# smart-home_matherboard.net
KiCad netlist of a schematic drawn in EAGLE
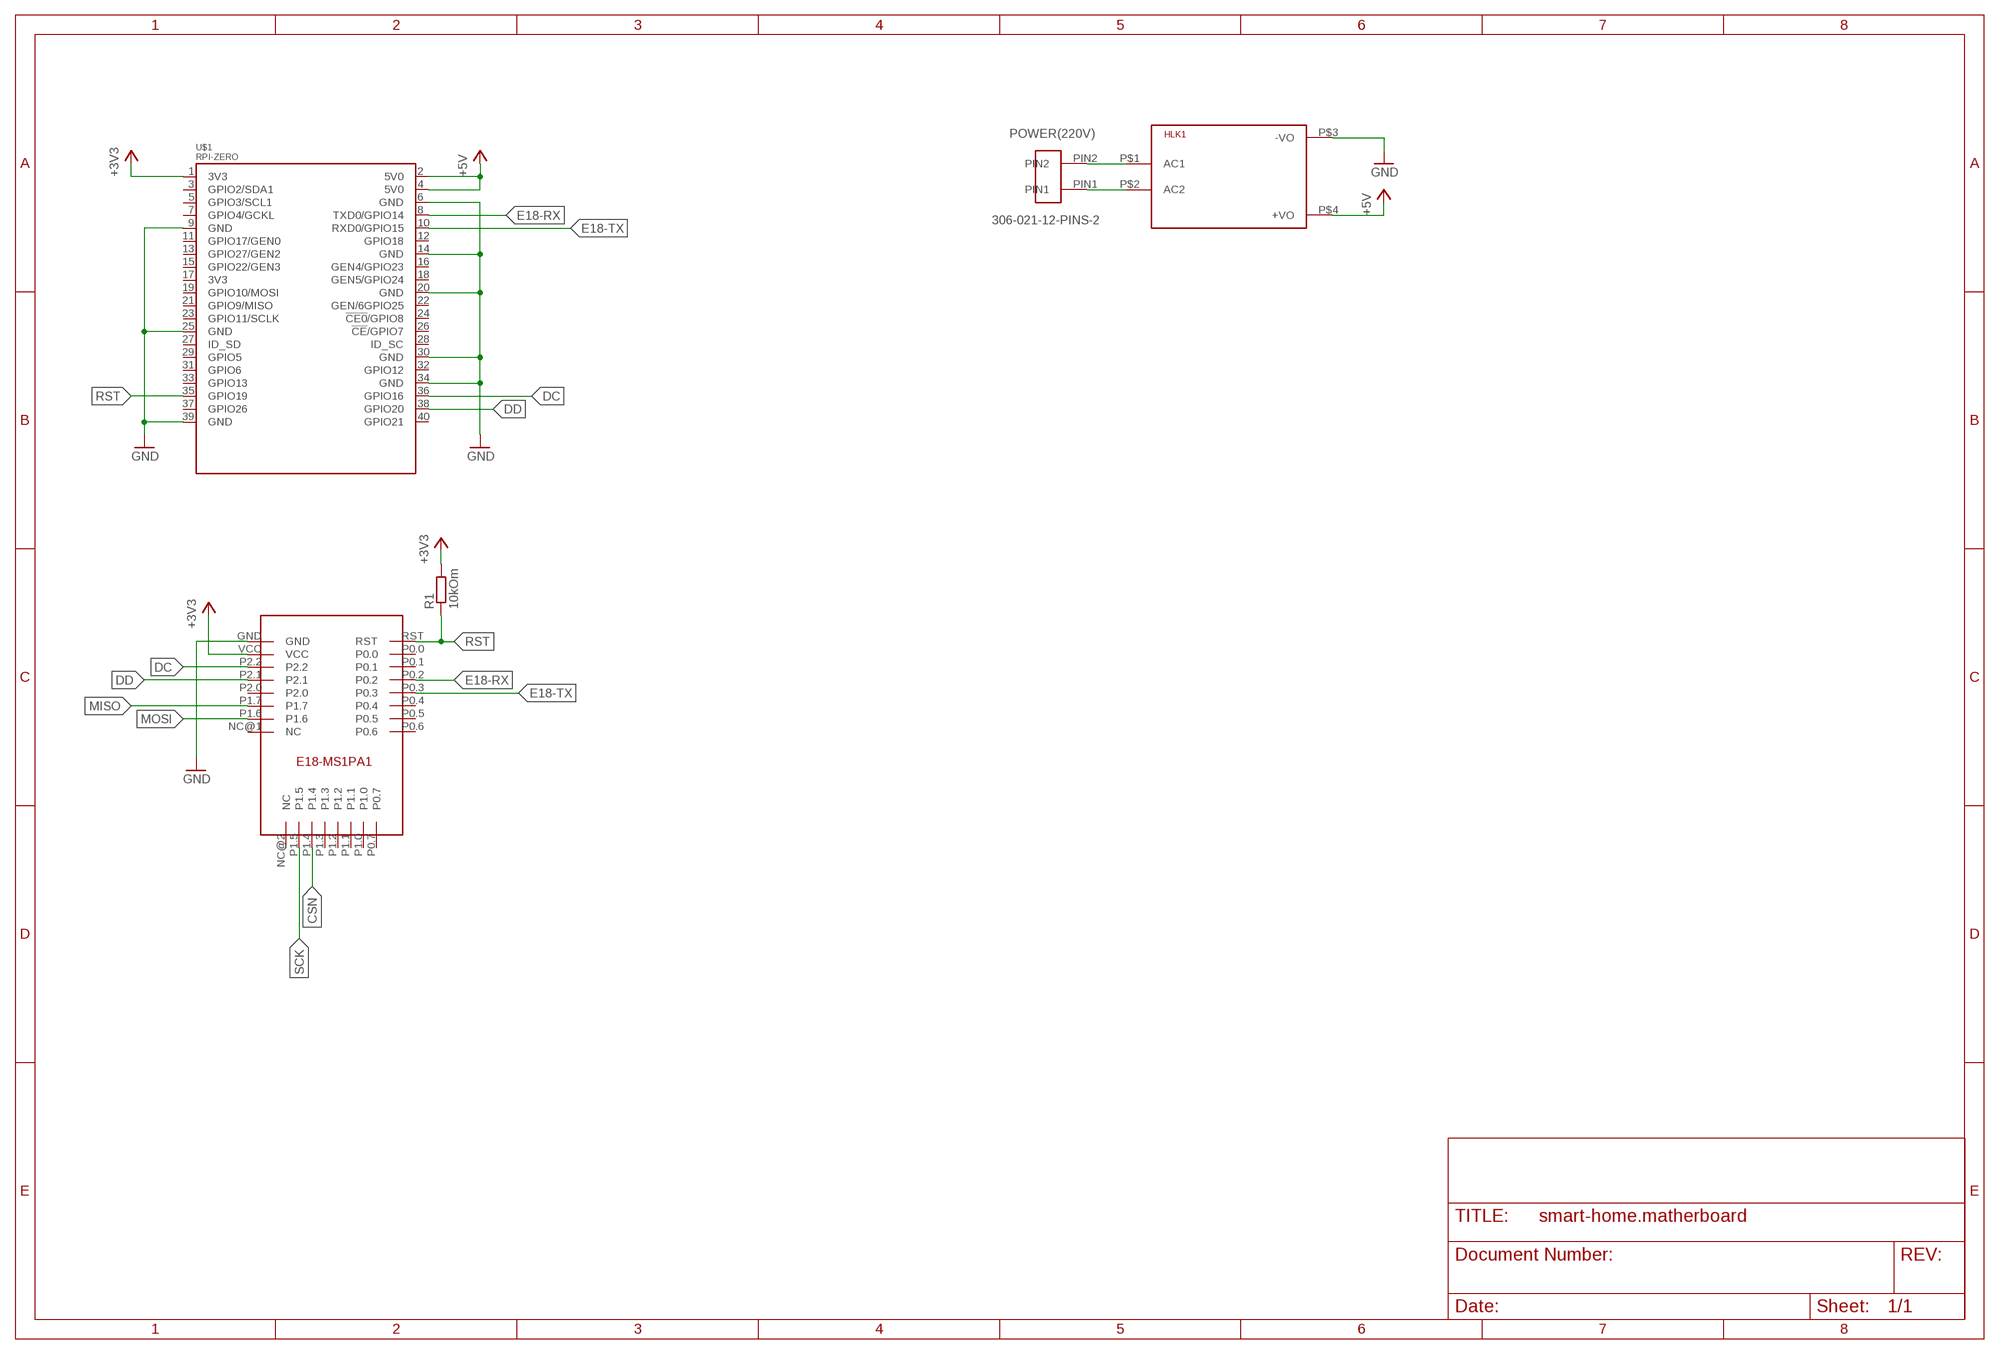
[diagram p0: schematic, sheet 1]

(export (version "E")
  (design (tool "Eeschema 10.0.6"))
  (components
    (comp (ref "HLK1")
      (value "HLK-PM013W")
      (footprint "eagle-import:HLK-PM01")
      (libsource (lib "eagle-import") (part "HLK-PM013W"))
    )
    (comp (ref "POWER(220V)")
      (value "306-021-12-PINS-2")
      (footprint "eagle-import:SERIA-306-2PIN")
      (libsource (lib "eagle-import") (part "306-021-12-PINS-2"))
    )
    (comp (ref "R1")
      (value "10kOm")
      (footprint "eagle-import:R0603")
      (libsource (lib "eagle-import") (part "R-EU_R0603"))
    )
    (comp (ref "U$1")
      (value "RPI-ZERO")
      (footprint "eagle-import:RASPBERRYPI_BASTELSTUBE_V13_RASPI_BOARD_B+_FULL")
      (libsource (lib "eagle-import") (part "RPI-ZERO"))
    )
    (comp (ref "U$3")
      (value "E18-MS1PA1IPX")
      (footprint "eagle-import:E18-MS1PA1-IPX")
      (libsource (lib "eagle-import") (part "E18-MS1PA1IPX"))
    )
  )
  (nets
    (net (code "1") (name "+3V3") (class "Default")
      (node (ref "R1") (pin "2") (pinfunction "2_2") (pintype "passive"))
      (node (ref "U$1") (pin "1") (pinfunction "3V3_1") (pintype "power_in"))
      (node (ref "U$3") (pin "VCC") (pinfunction "VCC_VCC") (pintype "bidirectional"))
    )
    (net (code "2") (name "+5V") (class "Default")
      (node (ref "HLK1") (pin "P$4") (pinfunction "+VO_P$4") (pintype "bidirectional"))
      (node (ref "U$1") (pin "2") (pinfunction "5V0_2") (pintype "power_in"))
      (node (ref "U$1") (pin "4") (pinfunction "5V0_4") (pintype "power_in"))
    )
    (net (code "3") (name "/3V3") (class "Default")
      (node (ref "U$1") (pin "17") (pinfunction "3V3_17") (pintype "power_in"))
    )
    (net (code "4") (name "CSN") (class "Default")
      (node (ref "U$3") (pin "P1.4") (pinfunction "P1.4_P1.4") (pintype "bidirectional"))
    )
    (net (code "5") (name "DC") (class "Default")
      (node (ref "U$1") (pin "36") (pinfunction "GPIO16_36") (pintype "bidirectional"))
      (node (ref "U$3") (pin "P2.2") (pinfunction "P2.2_P2.2") (pintype "bidirectional"))
    )
    (net (code "6") (name "DD") (class "Default")
      (node (ref "U$1") (pin "38") (pinfunction "GPIO20_38") (pintype "bidirectional"))
      (node (ref "U$3") (pin "P2.1") (pinfunction "P2.1_P2.1") (pintype "bidirectional"))
    )
    (net (code "7") (name "E18-RX") (class "Default")
      (node (ref "U$1") (pin "8") (pinfunction "TXD0/GPIO14_8") (pintype "bidirectional"))
      (node (ref "U$3") (pin "P0.2") (pinfunction "P0.2_P0.2") (pintype "bidirectional"))
    )
    (net (code "8") (name "E18-TX") (class "Default")
      (node (ref "U$1") (pin "10") (pinfunction "RXD0/GPIO15_10") (pintype "bidirectional"))
      (node (ref "U$3") (pin "P0.3") (pinfunction "P0.3_P0.3") (pintype "bidirectional"))
    )
    (net (code "9") (name "GND") (class "Default")
      (node (ref "HLK1") (pin "P$3") (pinfunction "-VO_P$3") (pintype "bidirectional"))
      (node (ref "U$1") (pin "14") (pinfunction "GND_14") (pintype "power_in"))
      (node (ref "U$1") (pin "20") (pinfunction "GND_20") (pintype "power_in"))
      (node (ref "U$1") (pin "25") (pinfunction "GND_25") (pintype "power_in"))
      (node (ref "U$1") (pin "30") (pinfunction "GND_30") (pintype "power_in"))
      (node (ref "U$1") (pin "34") (pinfunction "GND_34") (pintype "power_in"))
      (node (ref "U$1") (pin "39") (pinfunction "GND_39") (pintype "power_in"))
      (node (ref "U$1") (pin "6") (pinfunction "GND_6") (pintype "power_in"))
      (node (ref "U$1") (pin "9") (pinfunction "GND_9") (pintype "power_in"))
      (node (ref "U$3") (pin "GND") (pinfunction "GND_GND") (pintype "bidirectional"))
    )
    (net (code "10") (name "MISO") (class "Default")
      (node (ref "U$3") (pin "P1.7") (pinfunction "P1.7_P1.7") (pintype "bidirectional"))
    )
    (net (code "11") (name "MOSI") (class "Default")
      (node (ref "U$3") (pin "P1.6") (pinfunction "P1.6_P1.6") (pintype "bidirectional"))
    )
    (net (code "12") (name "Net-(HLK1-AC1)") (class "Default")
      (node (ref "HLK1") (pin "P$1") (pinfunction "AC1_P$1") (pintype "bidirectional"))
      (node (ref "POWER(220V)") (pin "PIN2") (pinfunction "PIN2_PIN2") (pintype "bidirectional"))
    )
    (net (code "13") (name "Net-(HLK1-AC2)") (class "Default")
      (node (ref "HLK1") (pin "P$2") (pinfunction "AC2_P$2") (pintype "bidirectional"))
      (node (ref "POWER(220V)") (pin "PIN1") (pinfunction "PIN1_PIN1") (pintype "bidirectional"))
    )
    (net (code "14") (name "RST") (class "Default")
      (node (ref "R1") (pin "1") (pinfunction "1_1") (pintype "passive"))
      (node (ref "U$1") (pin "35") (pinfunction "GPIO19_35") (pintype "bidirectional"))
      (node (ref "U$3") (pin "RST") (pinfunction "RST_RST") (pintype "bidirectional"))
    )
    (net (code "15") (name "SCK") (class "Default")
      (node (ref "U$3") (pin "P1.5") (pinfunction "P1.5_P1.5") (pintype "bidirectional"))
    )
    (net (code "16") (name "unconnected-(U$1-GEN4{slash}GPIO23-Pad16)") (class "Default")
      (node (ref "U$1") (pin "16") (pinfunction "GEN4/GPIO23_16") (pintype "bidirectional"))
    )
    (net (code "17") (name "unconnected-(U$1-GEN5{slash}GPIO24-Pad18)") (class "Default")
      (node (ref "U$1") (pin "18") (pinfunction "GEN5/GPIO24_18") (pintype "bidirectional"))
    )
    (net (code "18") (name "unconnected-(U$1-GEN{slash}6GPIO25-Pad22)") (class "Default")
      (node (ref "U$1") (pin "22") (pinfunction "GEN/6GPIO25_22") (pintype "bidirectional"))
    )
    (net (code "19") (name "unconnected-(U$1-GPIO2{slash}SDA1-Pad3)") (class "Default")
      (node (ref "U$1") (pin "3") (pinfunction "GPIO2/SDA1_3") (pintype "bidirectional"))
    )
    (net (code "20") (name "unconnected-(U$1-GPIO3{slash}SCL1-Pad5)") (class "Default")
      (node (ref "U$1") (pin "5") (pinfunction "GPIO3/SCL1_5") (pintype "bidirectional"))
    )
    (net (code "21") (name "unconnected-(U$1-GPIO4{slash}GCKL-Pad7)") (class "Default")
      (node (ref "U$1") (pin "7") (pinfunction "GPIO4/GCKL_7") (pintype "bidirectional"))
    )
    (net (code "22") (name "unconnected-(U$1-GPIO5-Pad29)") (class "Default")
      (node (ref "U$1") (pin "29") (pinfunction "GPIO5_29") (pintype "bidirectional"))
    )
    (net (code "23") (name "unconnected-(U$1-GPIO6-Pad31)") (class "Default")
      (node (ref "U$1") (pin "31") (pinfunction "GPIO6_31") (pintype "bidirectional"))
    )
    (net (code "24") (name "unconnected-(U$1-GPIO9{slash}MISO-Pad21)") (class "Default")
      (node (ref "U$1") (pin "21") (pinfunction "GPIO9/MISO_21") (pintype "bidirectional"))
    )
    (net (code "25") (name "unconnected-(U$1-GPIO10{slash}MOSI-Pad19)") (class "Default")
      (node (ref "U$1") (pin "19") (pinfunction "GPIO10/MOSI_19") (pintype "bidirectional"))
    )
    (net (code "26") (name "unconnected-(U$1-GPIO11{slash}SCLK-Pad23)") (class "Default")
      (node (ref "U$1") (pin "23") (pinfunction "GPIO11/SCLK_23") (pintype "bidirectional"))
    )
    (net (code "27") (name "unconnected-(U$1-GPIO12-Pad32)") (class "Default")
      (node (ref "U$1") (pin "32") (pinfunction "GPIO12_32") (pintype "bidirectional"))
    )
    (net (code "28") (name "unconnected-(U$1-GPIO13-Pad33)") (class "Default")
      (node (ref "U$1") (pin "33") (pinfunction "GPIO13_33") (pintype "bidirectional"))
    )
    (net (code "29") (name "unconnected-(U$1-GPIO17{slash}GEN0-Pad11)") (class "Default")
      (node (ref "U$1") (pin "11") (pinfunction "GPIO17/GEN0_11") (pintype "bidirectional"))
    )
    (net (code "30") (name "unconnected-(U$1-GPIO18-Pad12)") (class "Default")
      (node (ref "U$1") (pin "12") (pinfunction "GPIO18_12") (pintype "bidirectional"))
    )
    (net (code "31") (name "unconnected-(U$1-GPIO21-Pad40)") (class "Default")
      (node (ref "U$1") (pin "40") (pinfunction "GPIO21_40") (pintype "bidirectional"))
    )
    (net (code "32") (name "unconnected-(U$1-GPIO22{slash}GEN3-Pad15)") (class "Default")
      (node (ref "U$1") (pin "15") (pinfunction "GPIO22/GEN3_15") (pintype "bidirectional"))
    )
    (net (code "33") (name "unconnected-(U$1-GPIO26-Pad37)") (class "Default")
      (node (ref "U$1") (pin "37") (pinfunction "GPIO26_37") (pintype "bidirectional"))
    )
    (net (code "34") (name "unconnected-(U$1-GPIO27{slash}GEN2-Pad13)") (class "Default")
      (node (ref "U$1") (pin "13") (pinfunction "GPIO27/GEN2_13") (pintype "bidirectional"))
    )
    (net (code "35") (name "unconnected-(U$1-ID_SC-Pad28)") (class "Default")
      (node (ref "U$1") (pin "28") (pinfunction "ID_SC_28") (pintype "bidirectional"))
    )
    (net (code "36") (name "unconnected-(U$1-ID_SD-Pad27)") (class "Default")
      (node (ref "U$1") (pin "27") (pinfunction "ID_SD_27") (pintype "bidirectional"))
    )
    (net (code "37") (name "unconnected-(U$1-~{CE0}{slash}GPIO8-Pad24)") (class "Default")
      (node (ref "U$1") (pin "24") (pinfunction "~{CE0}/GPIO8_24") (pintype "bidirectional"))
    )
    (net (code "38") (name "unconnected-(U$1-~{CE}{slash}GPIO7-Pad26)") (class "Default")
      (node (ref "U$1") (pin "26") (pinfunction "~{CE}/GPIO7_26") (pintype "bidirectional"))
    )
    (net (code "39") (name "unconnected-(U$3-NC-PadNC@1)") (class "Default")
      (node (ref "U$3") (pin "NC@1") (pinfunction "NC_NC@1") (pintype "bidirectional"))
    )
    (net (code "40") (name "unconnected-(U$3-NC-PadNC@2)") (class "Default")
      (node (ref "U$3") (pin "NC@2") (pinfunction "NC_NC@2") (pintype "bidirectional"))
    )
    (net (code "41") (name "unconnected-(U$3-PadP0.0)") (class "Default")
      (node (ref "U$3") (pin "P0.0") (pinfunction "P0.0_P0.0") (pintype "bidirectional"))
    )
    (net (code "42") (name "unconnected-(U$3-PadP0.1)") (class "Default")
      (node (ref "U$3") (pin "P0.1") (pinfunction "P0.1_P0.1") (pintype "bidirectional"))
    )
    (net (code "43") (name "unconnected-(U$3-PadP0.4)") (class "Default")
      (node (ref "U$3") (pin "P0.4") (pinfunction "P0.4_P0.4") (pintype "bidirectional"))
    )
    (net (code "44") (name "unconnected-(U$3-PadP0.5)") (class "Default")
      (node (ref "U$3") (pin "P0.5") (pinfunction "P0.5_P0.5") (pintype "bidirectional"))
    )
    (net (code "45") (name "unconnected-(U$3-PadP0.6)") (class "Default")
      (node (ref "U$3") (pin "P0.6") (pinfunction "P0.6_P0.6") (pintype "bidirectional"))
    )
    (net (code "46") (name "unconnected-(U$3-PadP0.7)") (class "Default")
      (node (ref "U$3") (pin "P0.7") (pinfunction "P0.7_P0.7") (pintype "bidirectional"))
    )
    (net (code "47") (name "unconnected-(U$3-PadP1.0)") (class "Default")
      (node (ref "U$3") (pin "P1.0") (pinfunction "P1.0_P1.0") (pintype "bidirectional"))
    )
    (net (code "48") (name "unconnected-(U$3-PadP1.1)") (class "Default")
      (node (ref "U$3") (pin "P1.1") (pinfunction "P1.1_P1.1") (pintype "bidirectional"))
    )
    (net (code "49") (name "unconnected-(U$3-PadP1.2)") (class "Default")
      (node (ref "U$3") (pin "P1.2") (pinfunction "P1.2_P1.2") (pintype "bidirectional"))
    )
    (net (code "50") (name "unconnected-(U$3-PadP1.3)") (class "Default")
      (node (ref "U$3") (pin "P1.3") (pinfunction "P1.3_P1.3") (pintype "bidirectional"))
    )
    (net (code "51") (name "unconnected-(U$3-PadP2.0)") (class "Default")
      (node (ref "U$3") (pin "P2.0") (pinfunction "P2.0_P2.0") (pintype "bidirectional"))
    )
  )
)
